# Nuio_LeftKeyboard_Rev_E_5_KeyboardNRF.net
KiCad netlist of a schematic drawn in Altium Designer
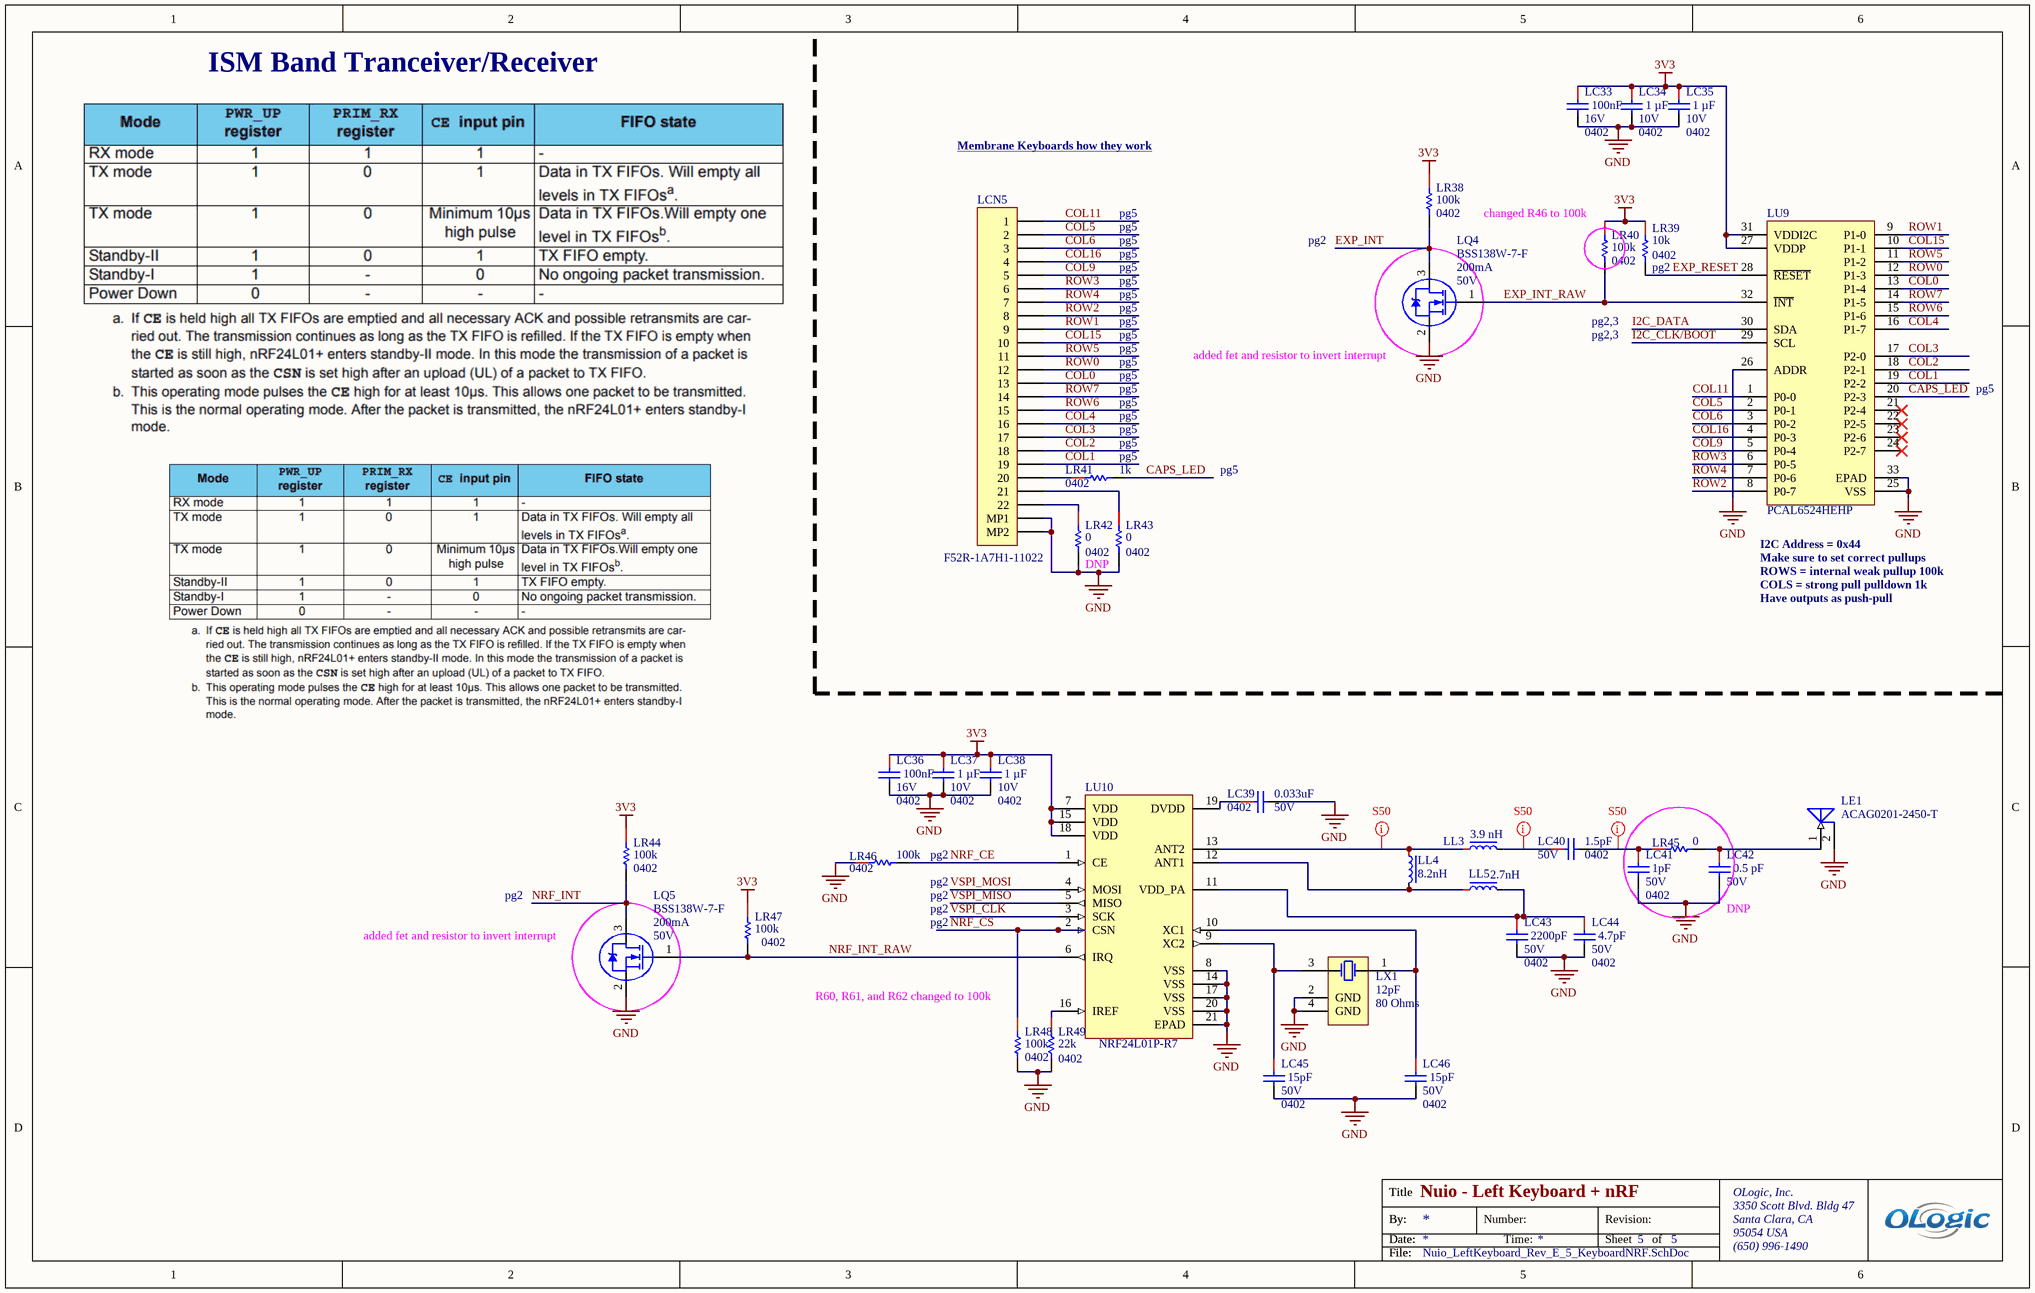
[diagram p0: Nuio_LeftKeyboard_Rev_E_5_KeyboardNRF.SchDoc]

(export (version "E")
  (design (tool "Eeschema 10.0.6"))
  (components
    (comp (ref "LC33")
      (value "CAP CER 0.1UF 16V X5R 0402")
      (footprint "CAPC0402(1005)_L")
      (description "±10% 16V Ceramic Capacitor X5R 0402 (1005 Metric)")
      (fields
        (field (name "PACKAGE (IMPERIAL)") "0402")
        (field (name "VOLTAGE (RATED)") "16V")
        (field (name "CAPACITANCE") "100nF")
        (field (name "MANUFACTURER") "Taiyo Yuden")
        (field (name "MANUFACTURER PART NUMBER") "EMK105BJ104KV-F")
      )
      (libsource (lib "OLogic Nexus Vault") (part "OL_Capacitor"))
    )
    (comp (ref "LC34")
      (value "CAP CER 1UF 10V X5R 0402")
      (footprint "CAPC0402(1005)_L")
      (description "±20% 10V Ceramic Capacitor X5R 0402 (1005 Metric)")
      (fields
        (field (name "PACKAGE (IMPERIAL)") "0402")
        (field (name "VOLTAGE (RATED)") "10V")
        (field (name "CAPACITANCE") "1 µF")
        (field (name "MANUFACTURER PART NUMBER") "CC0402MRX5R6BB105")
        (field (name "TOLERANCE") "±20%")
      )
      (libsource (lib "OLogic Nexus Vault") (part "OL_Capacitor"))
    )
    (comp (ref "LC35")
      (value "CAP CER 1UF 10V X5R 0402")
      (footprint "CAPC0402(1005)_L")
      (description "±20% 10V Ceramic Capacitor X5R 0402 (1005 Metric)")
      (fields
        (field (name "PACKAGE (IMPERIAL)") "0402")
        (field (name "VOLTAGE (RATED)") "10V")
        (field (name "CAPACITANCE") "1 µF")
        (field (name "MANUFACTURER PART NUMBER") "CC0402MRX5R6BB105")
        (field (name "TOLERANCE") "±20%")
      )
      (libsource (lib "OLogic Nexus Vault") (part "OL_Capacitor"))
    )
    (comp (ref "LC36")
      (value "CAP CER 0.1UF 16V X5R 0402")
      (footprint "CAPC0402(1005)_L")
      (description "±10% 16V Ceramic Capacitor X5R 0402 (1005 Metric)")
      (fields
        (field (name "PACKAGE (IMPERIAL)") "0402")
        (field (name "VOLTAGE (RATED)") "16V")
        (field (name "CAPACITANCE") "100nF")
        (field (name "MANUFACTURER") "Taiyo Yuden")
        (field (name "MANUFACTURER PART NUMBER") "EMK105BJ104KV-F")
      )
      (libsource (lib "OLogic Nexus Vault") (part "OL_Capacitor"))
    )
    (comp (ref "LC37")
      (value "CAP CER 1UF 10V X5R 0402")
      (footprint "CAPC0402(1005)_L")
      (description "±20% 10V Ceramic Capacitor X5R 0402 (1005 Metric)")
      (fields
        (field (name "PACKAGE (IMPERIAL)") "0402")
        (field (name "VOLTAGE (RATED)") "10V")
        (field (name "CAPACITANCE") "1 µF")
        (field (name "MANUFACTURER PART NUMBER") "CC0402MRX5R6BB105")
        (field (name "TOLERANCE") "±20%")
      )
      (libsource (lib "OLogic Nexus Vault") (part "OL_Capacitor"))
    )
    (comp (ref "LC38")
      (value "CAP CER 1UF 10V X5R 0402")
      (footprint "CAPC0402(1005)_L")
      (description "±20% 10V Ceramic Capacitor X5R 0402 (1005 Metric)")
      (fields
        (field (name "PACKAGE (IMPERIAL)") "0402")
        (field (name "VOLTAGE (RATED)") "10V")
        (field (name "CAPACITANCE") "1 µF")
        (field (name "MANUFACTURER PART NUMBER") "CC0402MRX5R6BB105")
        (field (name "TOLERANCE") "±20%")
      )
      (libsource (lib "OLogic Nexus Vault") (part "OL_Capacitor"))
    )
    (comp (ref "LC39")
      (value "0.033uF")
      (footprint "CAPC0402(1005)_L")
      (description "CAP CER 0.033UF 50V 10% X7R 0402")
      (fields
        (field (name "VOLTAGE (RATED)") "50V")
        (field (name "PACKAGE (IMPERIAL)") "0402")
        (field (name "TOLERANCE") "10%")
      )
      (libsource (lib "OLogic Nexus Vault") (part "=Capacitance"))
    )
    (comp (ref "LC40")
      (value "1.5pF")
      (footprint "CAPC0402(1005)_L")
      (description "CAP CER 1.5PF 50V NP0 0402")
      (fields
        (field (name "VOLTAGE (RATED)") "50V")
        (field (name "PACKAGE (IMPERIAL)") "0402")
        (field (name "TOLERANCE") "5%")
      )
      (libsource (lib "OLogic Nexus Vault") (part "=Capacitance"))
    )
    (comp (ref "LC41")
      (value "1pF")
      (footprint "CAPC0402(1005)_L")
      (description "CAP CER 1PF 50V NP0 0402")
      (fields
        (field (name "VOLTAGE (RATED)") "50V")
        (field (name "PACKAGE (IMPERIAL)") "0402")
        (field (name "TOLERANCE") "5%")
      )
      (libsource (lib "OLogic Nexus Vault") (part "=Capacitance"))
    )
    (comp (ref "LC42")
      (value "CAP CER 0.5PF 50V C0G/NP0 0402")
      (footprint "CAPC0402(1005)_L")
      (description "0.5 pF ±0.1pF 50V Ceramic Capacitor C0G, NP0 0402 (1005 Metric)")
      (fields
        (field (name "CAPACITANCE") "0.5 pF")
        (field (name "VOLTAGE - RATED") "50V")
        (field (name "TOLERANCE") "±0.1pF")
        (field (name "MANUFACTURER PART NUMBER") "QSCF500Q0R5B1GV001T")
      )
      (libsource (lib "OLogic Nexus Vault") (part "OL_Capacitor"))
    )
    (comp (ref "LC43")
      (value "2200pF")
      (footprint "CAPC0402(1005)_L")
      (description "CAP CER 2200PF 50V 10% X7R 0402")
      (fields
        (field (name "VOLTAGE (RATED)") "50V")
        (field (name "PACKAGE (IMPERIAL)") "0402")
        (field (name "TOLERANCE") "10%")
      )
      (libsource (lib "OLogic Nexus Vault") (part "=Capacitance"))
    )
    (comp (ref "LC44")
      (value "4.7pF")
      (footprint "CAPC0402(1005)_L")
      (description "CAP CER 4.7pF 50V 5% NP0 0402")
      (fields
        (field (name "VOLTAGE (RATED)") "50V")
        (field (name "PACKAGE (IMPERIAL)") "0402")
        (field (name "TOLERANCE") "5%")
      )
      (libsource (lib "OLogic Nexus Vault") (part "=Capacitance"))
    )
    (comp (ref "LC45")
      (value "15pF")
      (footprint "CAPC0402(1005)_L")
      (description "CAP CER 15PF 50V C0G/NP0 0402")
      (fields
        (field (name "VOLTAGE (RATED)") "50V")
        (field (name "PACKAGE (IMPERIAL)") "0402")
        (field (name "TOLERANCE") "5%")
      )
      (libsource (lib "OLogic Nexus Vault") (part "=Capacitance"))
    )
    (comp (ref "LC46")
      (value "15pF")
      (footprint "CAPC0402(1005)_L")
      (description "CAP CER 15PF 50V C0G/NP0 0402")
      (fields
        (field (name "VOLTAGE (RATED)") "50V")
        (field (name "PACKAGE (IMPERIAL)") "0402")
        (field (name "TOLERANCE") "5%")
      )
      (libsource (lib "OLogic Nexus Vault") (part "=Capacitance"))
    )
    (comp (ref "LCN5")
      (value "F52R-1A7H1-11022")
      (footprint "F52R-1A7H1-11022")
      (description "FLEX CONNECTOR, 1.00MM PITCH, HE")
      (fields (field (name "MANUFACTURER") "Amphenol ICC (FCI)"))
      (libsource (lib "OLogic Nexus Vault") (part "F52R-1A7H1-11022"))
    )
    (comp (ref "LE1")
      (value "ACAG0201-2450-T")
      (footprint "ACAG0201-2450-T")
      (description "RF ANT 2.4GHZ CHIP SOLDER SMD")
      (fields (field (name "MANUFACTURER") "Abracon LLC"))
      (libsource (lib "OLogic Nexus Vault") (part "RF ANT Trace - OLogic"))
    )
    (comp (ref "LL3")
      (value "FIXED IND 3.9NH 0402")
      (footprint "FP-LQG15HH_02-IPC_C")
      (description "Inductor RF Chip 0.0039uH 0.1nH 100MHz 8Q-Factor Air 0.75A 0.14Ohm DCR 0402 T/R")
      (fields
        (field (name "INDUCTANCE") "3.9 nH")
        (field (name "MANUFACTURER PART NUMBER") "Murata Electronics")
        (field (name "MANUFACTURER") "LQG15HS3N9B02D")
      )
      (libsource (lib "OLogic Nexus Vault") (part "OL_Inductor_sm"))
    )
    (comp (ref "LL4")
      (value "FIXED IND 8.2NH 550MA 240MOHM SM")
      (footprint "Inductor0402(1005)_L")
      (description "8.2 nH Unshielded Multilayer Inductor 550 mA 240mOhm Max 0402 (1005 Metric)")
      (fields
        (field (name "INDUCTANCE") "8.2nH")
        (field (name "MANUFACTURER PART NUMBER") "LQG15HS8N2J02D")
        (field (name "MANUFACTURER") "Murata Electronics")
      )
      (libsource (lib "OLogic Nexus Vault") (part "OL_Inductor_sm"))
    )
    (comp (ref "LL5")
      (value "FIXED IND 2.7NH 800MA 150MOHM SM")
      (footprint "Inductor0402(1005)_L")
      (description "2.7 nH Unshielded Multilayer Inductor 800 mA 150mOhm Max 0402 (1005 Metric)")
      (fields
        (field (name "INDUCTANCE") "2.7nH")
        (field (name "MANUFACTURER PART NUMBER") "LQG15HS2N7S02D")
        (field (name "MANUFACTURER") "Murata Electronics")
      )
      (libsource (lib "OLogic Nexus Vault") (part "OL_Inductor_sm"))
    )
    (comp (ref "LQ4")
      (value "BSS138W-7-F")
      (footprint "DIOD-SOT323-3_V")
      (description "DIODES INC. - BSS138W-7-F. - BSS FAMILY SOT323 T&R 3K ROHS COMPLIANT: YES")
      (fields
        (field (name "VOLTAGE") "50V")
        (field (name "POWER") "200mW")
        (field (name "CONTINUOUS DRAIN CURRENT (ID)") "200mA")
        (field (name "VOLTAGE RATING (DC)") "50V")
      )
      (libsource (lib "OLogic Nexus Vault") (part "OL_NFET_GSD"))
    )
    (comp (ref "LQ5")
      (value "BSS138W-7-F")
      (footprint "DIOD-SOT323-3_V")
      (description "DIODES INC. - BSS138W-7-F. - BSS FAMILY SOT323 T&R 3K ROHS COMPLIANT: YES")
      (fields
        (field (name "VOLTAGE") "50V")
        (field (name "POWER") "200mW")
        (field (name "CONTINUOUS DRAIN CURRENT (ID)") "200mA")
        (field (name "VOLTAGE RATING (DC)") "50V")
      )
      (libsource (lib "OLogic Nexus Vault") (part "OL_NFET_GSD"))
    )
    (comp (ref "LR38")
      (value "100k")
      (footprint "RESC0402(1005)_L")
      (description "±1% 0.063W, 1/16W Chip Resistor 0402 (1005 Metric) Moisture Resistant Thick Film")
      (fields
        (field (name "CASE CODE (IMPERIAL)") "0402")
        (field (name "TOLERANCE") "1%")
        (field (name "MANUFACTURER") "YAGEO")
      )
      (libsource (lib "OLogic Nexus Vault") (part "=Resistance"))
    )
    (comp (ref "LR39")
      (value "RES SMD 10K OHM 1% 1/16W 0402")
      (footprint "RESC0402(1005)_L")
      (description "10 kOhms ±1% 0.063W, 1/16W Chip Resistor 0402 (1005 Metric) Thin Film")
      (fields
        (field (name "PACKAGE (IMPERIAL)") "0402")
        (field (name "RESISTANCE") "10k")
        (field (name "POWER") "63mW")
        (field (name "TOLERANCE") "1%")
      )
      (libsource (lib "OLogic Nexus Vault") (part "=Resistance"))
    )
    (comp (ref "LR40")
      (value "100k")
      (footprint "RESC0402(1005)_L")
      (description "±1% 0.063W, 1/16W Chip Resistor 0402 (1005 Metric) Moisture Resistant Thick Film")
      (fields
        (field (name "CASE CODE (IMPERIAL)") "0402")
        (field (name "TOLERANCE") "1%")
        (field (name "MANUFACTURER") "YAGEO")
      )
      (libsource (lib "OLogic Nexus Vault") (part "=Resistance"))
    )
    (comp (ref "LR41")
      (value "RES SMD 1K OHM 1% 1/16W 0402")
      (footprint "RESC0402(1005)_L")
      (fields
        (field (name "RESISTANCE") "1k")
        (field (name "PACKAGE (IMPERIAL)") "0402")
        (field (name "POWER") "63mW")
        (field (name "MANUFACTURER") "Yageo")
        (field (name "TOLERANCE") "1%")
      )
      (libsource (lib "OLogic Nexus Vault") (part "OL_Resistor"))
    )
    (comp (ref "LR42")
      (value "RES 0 OHM JUMPER 1/16W 0402")
      (footprint "RESC0402(1005)_L")
      (description "0 Ohms Jumper Chip Resistor 0402 (1005 Metric) Automotive AEC-Q200 Thick Film")
      (fields
        (field (name "PACKAGE (IMPERIAL)") "0402")
        (field (name "RESISTANCE") "0")
        (field (name "POWER") "63mW")
        (field (name "TOLERANCE") "0%")
      )
      (libsource (lib "OLogic Nexus Vault") (part "=Resistance"))
    )
    (comp (ref "LR43")
      (value "RES 0 OHM JUMPER 1/16W 0402")
      (footprint "RESC0402(1005)_L")
      (description "0 Ohms Jumper Chip Resistor 0402 (1005 Metric) Automotive AEC-Q200 Thick Film")
      (fields
        (field (name "PACKAGE (IMPERIAL)") "0402")
        (field (name "RESISTANCE") "0")
        (field (name "POWER") "63mW")
        (field (name "TOLERANCE") "0%")
      )
      (libsource (lib "OLogic Nexus Vault") (part "=Resistance"))
    )
    (comp (ref "LR44")
      (value "100k")
      (footprint "RESC0402(1005)_L")
      (description "±1% 0.063W, 1/16W Chip Resistor 0402 (1005 Metric) Moisture Resistant Thick Film")
      (fields
        (field (name "CASE CODE (IMPERIAL)") "0402")
        (field (name "TOLERANCE") "1%")
        (field (name "MANUFACTURER") "YAGEO")
      )
      (libsource (lib "OLogic Nexus Vault") (part "=Resistance"))
    )
    (comp (ref "LR45")
      (value "RES 0 OHM JUMPER 1/16W 0402")
      (footprint "RESC0402(1005)_L")
      (description "0 Ohms Jumper Chip Resistor 0402 (1005 Metric) Automotive AEC-Q200 Thick Film")
      (fields (field (name "RESISTANCE") "0") (field (name "POWER") "63mW") (field (name "TOLERANCE") "0%"))
      (libsource (lib "OLogic Nexus Vault") (part "=Resistance"))
    )
    (comp (ref "LR46")
      (value "100k")
      (footprint "RESC0402(1005)_L")
      (description "±1% 0.063W, 1/16W Chip Resistor 0402 (1005 Metric) Moisture Resistant Thick Film")
      (fields
        (field (name "CASE CODE (IMPERIAL)") "0402")
        (field (name "TOLERANCE") "1%")
        (field (name "MANUFACTURER") "YAGEO")
      )
      (libsource (lib "OLogic Nexus Vault") (part "=Resistance"))
    )
    (comp (ref "LR47")
      (value "100k")
      (footprint "RESC0402(1005)_L")
      (description "±1% 0.063W, 1/16W Chip Resistor 0402 (1005 Metric) Moisture Resistant Thick Film")
      (fields
        (field (name "CASE CODE (IMPERIAL)") "0402")
        (field (name "TOLERANCE") "1%")
        (field (name "MANUFACTURER") "YAGEO")
      )
      (libsource (lib "OLogic Nexus Vault") (part "=Resistance"))
    )
    (comp (ref "LR48")
      (value "100k")
      (footprint "RESC0402(1005)_L")
      (description "±1% 0.063W, 1/16W Chip Resistor 0402 (1005 Metric) Moisture Resistant Thick Film")
      (fields
        (field (name "CASE CODE (IMPERIAL)") "0402")
        (field (name "TOLERANCE") "1%")
        (field (name "MANUFACTURER") "YAGEO")
      )
      (libsource (lib "OLogic Nexus Vault") (part "=Resistance"))
    )
    (comp (ref "LR49")
      (value "22K")
      (footprint "RESC0402(1005)_L")
      (description "RES SMD 22K OHM 1% 1/16W 0402")
      (fields
        (field (name "PACKAGE (IMPERIAL)") "0402")
        (field (name "RESISTANCE") "22k")
        (field (name "POWER") "63mW")
        (field (name "TOLERANCE") "1%")
      )
      (libsource (lib "OLogic Nexus Vault") (part "=Resistance"))
    )
    (comp (ref "LU9")
      (value "PCAL6524HEHP")
      (footprint "QFN50P500X500X60_HS-33N")
      (description "Ultra low-voltage translating 24-bit Fm+ I²C-bus/SMBus I/O expander")
      (libsource (lib "OLogic Nexus Vault") (part "PCAL6524HEHP"))
    )
    (comp (ref "LU10")
      (value "NRF24L01P-R7")
      (footprint "QFN50P400X400X95_HS-21N")
      (description "IC RF TXRX ISM>1GHZ 20VFQFN")
      (fields (field (name "MANUFACTURER") "Nordic Semiconductor ASA"))
      (libsource (lib "OLogic Nexus Vault") (part "NRF24L01P-R7"))
    )
    (comp (ref "LX1")
      (value "ECS-160-12-33-AGN-TR3")
      (footprint "ECS-160-12-33-AGN-TR3")
      (description "CRYSTAL 16.0000MHZ 12PF SMD")
      (fields
        (field (name "LOAD CAPACITANCE") "12pF")
        (field (name "ESR") "80 Ohms")
        (field (name "MANUFACTURER") "ECS Inc.")
      )
      (libsource (lib "OLogic Nexus Vault") (part "OL_Crystal"))
    )
  )
  (nets
    (net (code "1") (name "/CAPS_LED") (class "Default")
      (node (ref "LR41") (pin "2") (pinfunction "2_2") (pintype "passive"))
      (node (ref "LU9") (pin "20") (pinfunction "P2-3_20") (pintype "passive"))
    )
    (net (code "2") (name "/COL0") (class "Default")
      (node (ref "LCN5") (pin "13") (pinfunction "13_13") (pintype "passive"))
      (node (ref "LU9") (pin "13") (pinfunction "P1-4_13") (pintype "passive"))
    )
    (net (code "3") (name "/COL1") (class "Default")
      (node (ref "LCN5") (pin "19") (pinfunction "19_19") (pintype "passive"))
      (node (ref "LU9") (pin "19") (pinfunction "P2-2_19") (pintype "passive"))
    )
    (net (code "4") (name "/COL2") (class "Default")
      (node (ref "LCN5") (pin "18") (pinfunction "18_18") (pintype "passive"))
      (node (ref "LU9") (pin "18") (pinfunction "P2-1_18") (pintype "passive"))
    )
    (net (code "5") (name "/COL3") (class "Default")
      (node (ref "LCN5") (pin "17") (pinfunction "17_17") (pintype "passive"))
      (node (ref "LU9") (pin "17") (pinfunction "P2-0_17") (pintype "passive"))
    )
    (net (code "6") (name "/COL4") (class "Default")
      (node (ref "LCN5") (pin "16") (pinfunction "16_16") (pintype "passive"))
      (node (ref "LU9") (pin "16") (pinfunction "P1-7_16") (pintype "passive"))
    )
    (net (code "7") (name "/COL5") (class "Default")
      (node (ref "LCN5") (pin "2") (pinfunction "2_2") (pintype "passive"))
      (node (ref "LU9") (pin "2") (pinfunction "P0-1_2") (pintype "passive"))
    )
    (net (code "8") (name "/COL6") (class "Default")
      (node (ref "LCN5") (pin "3") (pinfunction "3_3") (pintype "passive"))
      (node (ref "LU9") (pin "3") (pinfunction "P0-2_3") (pintype "passive"))
    )
    (net (code "9") (name "/COL9") (class "Default")
      (node (ref "LCN5") (pin "5") (pinfunction "5_5") (pintype "passive"))
      (node (ref "LU9") (pin "5") (pinfunction "P0-4_5") (pintype "passive"))
    )
    (net (code "10") (name "/COL11") (class "Default")
      (node (ref "LCN5") (pin "1") (pinfunction "1_1") (pintype "passive"))
      (node (ref "LU9") (pin "1") (pinfunction "P0-0_1") (pintype "passive"))
    )
    (net (code "11") (name "/COL15") (class "Default")
      (node (ref "LCN5") (pin "10") (pinfunction "10_10") (pintype "passive"))
      (node (ref "LU9") (pin "10") (pinfunction "P1-1_10") (pintype "passive"))
    )
    (net (code "12") (name "/COL16") (class "Default")
      (node (ref "LCN5") (pin "4") (pinfunction "4_4") (pintype "passive"))
      (node (ref "LU9") (pin "4") (pinfunction "P0-3_4") (pintype "passive"))
    )
    (net (code "13") (name "/EXP_INT") (class "Default")
      (node (ref "LQ4") (pin "3") (pinfunction "D_3") (pintype "passive"))
      (node (ref "LR38") (pin "2") (pinfunction "2_2") (pintype "passive"))
    )
    (net (code "14") (name "/EXP_INT_RAW") (class "Default")
      (node (ref "LQ4") (pin "1") (pinfunction "G_1") (pintype "passive"))
      (node (ref "LR40") (pin "2") (pinfunction "2_2") (pintype "passive"))
      (node (ref "LU9") (pin "32") (pinfunction "~{INT}_32") (pintype "passive"))
    )
    (net (code "15") (name "/EXP_RESET") (class "Default")
      (node (ref "LR39") (pin "2") (pinfunction "2_2") (pintype "passive"))
      (node (ref "LU9") (pin "28") (pinfunction "~{RESET}_28") (pintype "passive"))
    )
    (net (code "16") (name "/I2C_CLK{slash}BOOT") (class "Default")
      (node (ref "LU9") (pin "29") (pinfunction "SCL_29") (pintype "passive"))
    )
    (net (code "17") (name "/I2C_DATA") (class "Default")
      (node (ref "LU9") (pin "30") (pinfunction "SDA_30") (pintype "passive"))
    )
    (net (code "18") (name "/NRF_CE") (class "Default")
      (node (ref "LR46") (pin "2") (pinfunction "2_2") (pintype "passive"))
      (node (ref "LU10") (pin "1") (pinfunction "CE_1") (pintype "input"))
    )
    (net (code "19") (name "/NRF_CS") (class "Default")
      (node (ref "LR48") (pin "1") (pinfunction "1_1") (pintype "passive"))
      (node (ref "LU10") (pin "2") (pinfunction "CSN_2") (pintype "input"))
    )
    (net (code "20") (name "/NRF_INT") (class "Default")
      (node (ref "LQ5") (pin "3") (pinfunction "D_3") (pintype "passive"))
      (node (ref "LR44") (pin "2") (pinfunction "2_2") (pintype "passive"))
    )
    (net (code "21") (name "/NRF_INT_RAW") (class "Default")
      (node (ref "LQ5") (pin "1") (pinfunction "G_1") (pintype "passive"))
      (node (ref "LR47") (pin "2") (pinfunction "2_2") (pintype "passive"))
      (node (ref "LU10") (pin "6") (pinfunction "IRQ_6") (pintype "output"))
    )
    (net (code "22") (name "/ROW0") (class "Default")
      (node (ref "LCN5") (pin "12") (pinfunction "12_12") (pintype "passive"))
      (node (ref "LU9") (pin "12") (pinfunction "P1-3_12") (pintype "passive"))
    )
    (net (code "23") (name "/ROW1") (class "Default")
      (node (ref "LCN5") (pin "9") (pinfunction "9_9") (pintype "passive"))
      (node (ref "LU9") (pin "9") (pinfunction "P1-0_9") (pintype "passive"))
    )
    (net (code "24") (name "/ROW2") (class "Default")
      (node (ref "LCN5") (pin "8") (pinfunction "8_8") (pintype "passive"))
      (node (ref "LU9") (pin "8") (pinfunction "P0-7_8") (pintype "passive"))
    )
    (net (code "25") (name "/ROW3") (class "Default")
      (node (ref "LCN5") (pin "6") (pinfunction "6_6") (pintype "passive"))
      (node (ref "LU9") (pin "6") (pinfunction "P0-5_6") (pintype "passive"))
    )
    (net (code "26") (name "/ROW4") (class "Default")
      (node (ref "LCN5") (pin "7") (pinfunction "7_7") (pintype "passive"))
      (node (ref "LU9") (pin "7") (pinfunction "P0-6_7") (pintype "passive"))
    )
    (net (code "27") (name "/ROW5") (class "Default")
      (node (ref "LCN5") (pin "11") (pinfunction "11_11") (pintype "passive"))
      (node (ref "LU9") (pin "11") (pinfunction "P1-2_11") (pintype "passive"))
    )
    (net (code "28") (name "/ROW6") (class "Default")
      (node (ref "LCN5") (pin "15") (pinfunction "15_15") (pintype "passive"))
      (node (ref "LU9") (pin "15") (pinfunction "P1-6_15") (pintype "passive"))
    )
    (net (code "29") (name "/ROW7") (class "Default")
      (node (ref "LCN5") (pin "14") (pinfunction "14_14") (pintype "passive"))
      (node (ref "LU9") (pin "14") (pinfunction "P1-5_14") (pintype "passive"))
    )
    (net (code "30") (name "/VSPI_CLK") (class "Default")
      (node (ref "LU10") (pin "3") (pinfunction "SCK_3") (pintype "input"))
    )
    (net (code "31") (name "/VSPI_MISO") (class "Default")
      (node (ref "LU10") (pin "5") (pinfunction "MISO_5") (pintype "output"))
    )
    (net (code "32") (name "/VSPI_MOSI") (class "Default")
      (node (ref "LU10") (pin "4") (pinfunction "MOSI_4") (pintype "input"))
    )
    (net (code "33") (name "3V3") (class "Default")
      (node (ref "LC33") (pin "1") (pinfunction "1_1") (pintype "passive"))
      (node (ref "LC34") (pin "1") (pinfunction "1_1") (pintype "passive"))
      (node (ref "LC35") (pin "1") (pinfunction "1_1") (pintype "passive"))
      (node (ref "LC36") (pin "1") (pinfunction "1_1") (pintype "passive"))
      (node (ref "LC37") (pin "1") (pinfunction "1_1") (pintype "passive"))
      (node (ref "LC38") (pin "1") (pinfunction "1_1") (pintype "passive"))
      (node (ref "LR38") (pin "1") (pinfunction "1_1") (pintype "passive"))
      (node (ref "LR39") (pin "1") (pinfunction "1_1") (pintype "passive"))
      (node (ref "LR40") (pin "1") (pinfunction "1_1") (pintype "passive"))
      (node (ref "LR44") (pin "1") (pinfunction "1_1") (pintype "passive"))
      (node (ref "LR47") (pin "1") (pinfunction "1_1") (pintype "passive"))
      (node (ref "LU10") (pin "15") (pinfunction "VDD_15") (pintype "power_in"))
      (node (ref "LU10") (pin "18") (pinfunction "VDD_18") (pintype "power_in"))
      (node (ref "LU10") (pin "7") (pinfunction "VDD_7") (pintype "power_in"))
      (node (ref "LU9") (pin "27") (pinfunction "VDDP_27") (pintype "passive"))
      (node (ref "LU9") (pin "31") (pinfunction "VDDI2C_31") (pintype "passive"))
    )
    (net (code "34") (name "GND") (class "Default")
      (node (ref "LC33") (pin "2") (pinfunction "2_2") (pintype "passive"))
      (node (ref "LC34") (pin "2") (pinfunction "2_2") (pintype "passive"))
      (node (ref "LC35") (pin "2") (pinfunction "2_2") (pintype "passive"))
      (node (ref "LC36") (pin "2") (pinfunction "2_2") (pintype "passive"))
      (node (ref "LC37") (pin "2") (pinfunction "2_2") (pintype "passive"))
      (node (ref "LC38") (pin "2") (pinfunction "2_2") (pintype "passive"))
      (node (ref "LC39") (pin "2") (pinfunction "2_2") (pintype "passive"))
      (node (ref "LC41") (pin "2") (pinfunction "2_2") (pintype "passive"))
      (node (ref "LC42") (pin "2") (pinfunction "2_2") (pintype "passive"))
      (node (ref "LC43") (pin "2") (pinfunction "2_2") (pintype "passive"))
      (node (ref "LC44") (pin "2") (pinfunction "2_2") (pintype "passive"))
      (node (ref "LC45") (pin "2") (pinfunction "2_2") (pintype "passive"))
      (node (ref "LC46") (pin "2") (pinfunction "2_2") (pintype "passive"))
      (node (ref "LCN5") (pin "MP1") (pinfunction "MP1_MP1") (pintype "passive"))
      (node (ref "LCN5") (pin "MP2") (pinfunction "MP2_MP2") (pintype "passive"))
      (node (ref "LE1") (pin "2") (pinfunction "GND_2") (pintype "power_in"))
      (node (ref "LQ4") (pin "2") (pinfunction "S_2") (pintype "passive"))
      (node (ref "LQ5") (pin "2") (pinfunction "S_2") (pintype "passive"))
      (node (ref "LR42") (pin "2") (pinfunction "2_2") (pintype "passive"))
      (node (ref "LR43") (pin "2") (pinfunction "2_2") (pintype "passive"))
      (node (ref "LR46") (pin "1") (pinfunction "1_1") (pintype "passive"))
      (node (ref "LR48") (pin "2") (pinfunction "2_2") (pintype "passive"))
      (node (ref "LR49") (pin "2") (pinfunction "2_2") (pintype "passive"))
      (node (ref "LU10") (pin "14") (pinfunction "VSS_14") (pintype "power_in"))
      (node (ref "LU10") (pin "17") (pinfunction "VSS_17") (pintype "power_in"))
      (node (ref "LU10") (pin "20") (pinfunction "VSS_20") (pintype "power_in"))
      (node (ref "LU10") (pin "21") (pinfunction "EPAD_21") (pintype "power_in"))
      (node (ref "LU10") (pin "8") (pinfunction "VSS_8") (pintype "power_in"))
      (node (ref "LU9") (pin "25") (pinfunction "VSS_25") (pintype "passive"))
      (node (ref "LU9") (pin "26") (pinfunction "ADDR_26") (pintype "passive"))
      (node (ref "LU9") (pin "33") (pinfunction "EPAD_33") (pintype "passive"))
      (node (ref "LX1") (pin "2") (pinfunction "GND_2") (pintype "passive"))
      (node (ref "LX1") (pin "4") (pinfunction "GND_4") (pintype "passive"))
    )
    (net (code "35") (name "Net-(LC40-Pad1)") (class "Default")
      (node (ref "LC40") (pin "1") (pinfunction "1_1") (pintype "passive"))
      (node (ref "LL3") (pin "2") (pinfunction "2_2") (pintype "passive"))
    )
    (net (code "36") (name "Net-(LC40-Pad2)") (class "Default")
      (node (ref "LC40") (pin "2") (pinfunction "2_2") (pintype "passive"))
      (node (ref "LC41") (pin "1") (pinfunction "1_1") (pintype "passive"))
      (node (ref "LR45") (pin "1") (pinfunction "1_1") (pintype "passive"))
    )
    (net (code "37") (name "Net-(LCN5-Pad20)") (class "Default")
      (node (ref "LCN5") (pin "20") (pinfunction "20_20") (pintype "passive"))
      (node (ref "LR41") (pin "1") (pinfunction "1_1") (pintype "passive"))
    )
    (net (code "38") (name "Net-(LCN5-Pad21)") (class "Default")
      (node (ref "LCN5") (pin "21") (pinfunction "21_21") (pintype "passive"))
      (node (ref "LR43") (pin "1") (pinfunction "1_1") (pintype "passive"))
    )
    (net (code "39") (name "Net-(LCN5-Pad22)") (class "Default")
      (node (ref "LCN5") (pin "22") (pinfunction "22_22") (pintype "passive"))
      (node (ref "LR42") (pin "1") (pinfunction "1_1") (pintype "passive"))
    )
    (net (code "40") (name "Net-(LE1-INPUT)") (class "Default")
      (node (ref "LC42") (pin "1") (pinfunction "1_1") (pintype "passive"))
      (node (ref "LE1") (pin "1") (pinfunction "INPUT_1") (pintype "input"))
      (node (ref "LR45") (pin "2") (pinfunction "2_2") (pintype "passive"))
    )
    (net (code "41") (name "Net-(LU10-ANT1)") (class "Default")
      (node (ref "LL4") (pin "2") (pinfunction "2_2") (pintype "passive"))
      (node (ref "LL5") (pin "1") (pinfunction "1_1") (pintype "passive"))
      (node (ref "LU10") (pin "12") (pinfunction "ANT1_12") (pintype "passive"))
    )
    (net (code "42") (name "Net-(LU10-ANT2)") (class "Default")
      (node (ref "LL3") (pin "1") (pinfunction "1_1") (pintype "passive"))
      (node (ref "LL4") (pin "1") (pinfunction "1_1") (pintype "passive"))
      (node (ref "LU10") (pin "13") (pinfunction "ANT2_13") (pintype "passive"))
    )
    (net (code "43") (name "Net-(LU10-DVDD)") (class "Default")
      (node (ref "LC39") (pin "1") (pinfunction "1_1") (pintype "passive"))
      (node (ref "LU10") (pin "19") (pinfunction "DVDD_19") (pintype "power_in"))
    )
    (net (code "44") (name "Net-(LU10-IREF)") (class "Default")
      (node (ref "LR49") (pin "1") (pinfunction "1_1") (pintype "passive"))
      (node (ref "LU10") (pin "16") (pinfunction "IREF_16") (pintype "input"))
    )
    (net (code "45") (name "Net-(LU10-VDD_PA)") (class "Default")
      (node (ref "LC43") (pin "1") (pinfunction "1_1") (pintype "passive"))
      (node (ref "LC44") (pin "1") (pinfunction "1_1") (pintype "passive"))
      (node (ref "LL5") (pin "2") (pinfunction "2_2") (pintype "passive"))
      (node (ref "LU10") (pin "11") (pinfunction "VDD_PA_11") (pintype "power_in"))
    )
    (net (code "46") (name "Net-(LU10-XC1)") (class "Default")
      (node (ref "LC46") (pin "1") (pinfunction "1_1") (pintype "passive"))
      (node (ref "LU10") (pin "10") (pinfunction "XC1_10") (pintype "input"))
      (node (ref "LX1") (pin "1") (pinfunction "OSC1_1") (pintype "passive"))
    )
    (net (code "47") (name "Net-(LU10-XC2)") (class "Default")
      (node (ref "LC45") (pin "1") (pinfunction "1_1") (pintype "passive"))
      (node (ref "LU10") (pin "9") (pinfunction "XC2_9") (pintype "output"))
      (node (ref "LX1") (pin "3") (pinfunction "OSC2_3") (pintype "passive"))
    )
    (net (code "48") (name "unconnected-(LU9-P2-4-Pad21)") (class "Default")
      (node (ref "LU9") (pin "21") (pinfunction "P2-4_21") (pintype "passive+no_connect"))
    )
    (net (code "49") (name "unconnected-(LU9-P2-5-Pad22)") (class "Default")
      (node (ref "LU9") (pin "22") (pinfunction "P2-5_22") (pintype "passive+no_connect"))
    )
    (net (code "50") (name "unconnected-(LU9-P2-6-Pad23)") (class "Default")
      (node (ref "LU9") (pin "23") (pinfunction "P2-6_23") (pintype "passive+no_connect"))
    )
    (net (code "51") (name "unconnected-(LU9-P2-7-Pad24)") (class "Default")
      (node (ref "LU9") (pin "24") (pinfunction "P2-7_24") (pintype "passive+no_connect"))
    )
  )
)
